# Sheet1.net
KiCad netlist of a schematic drawn in Altium Designer
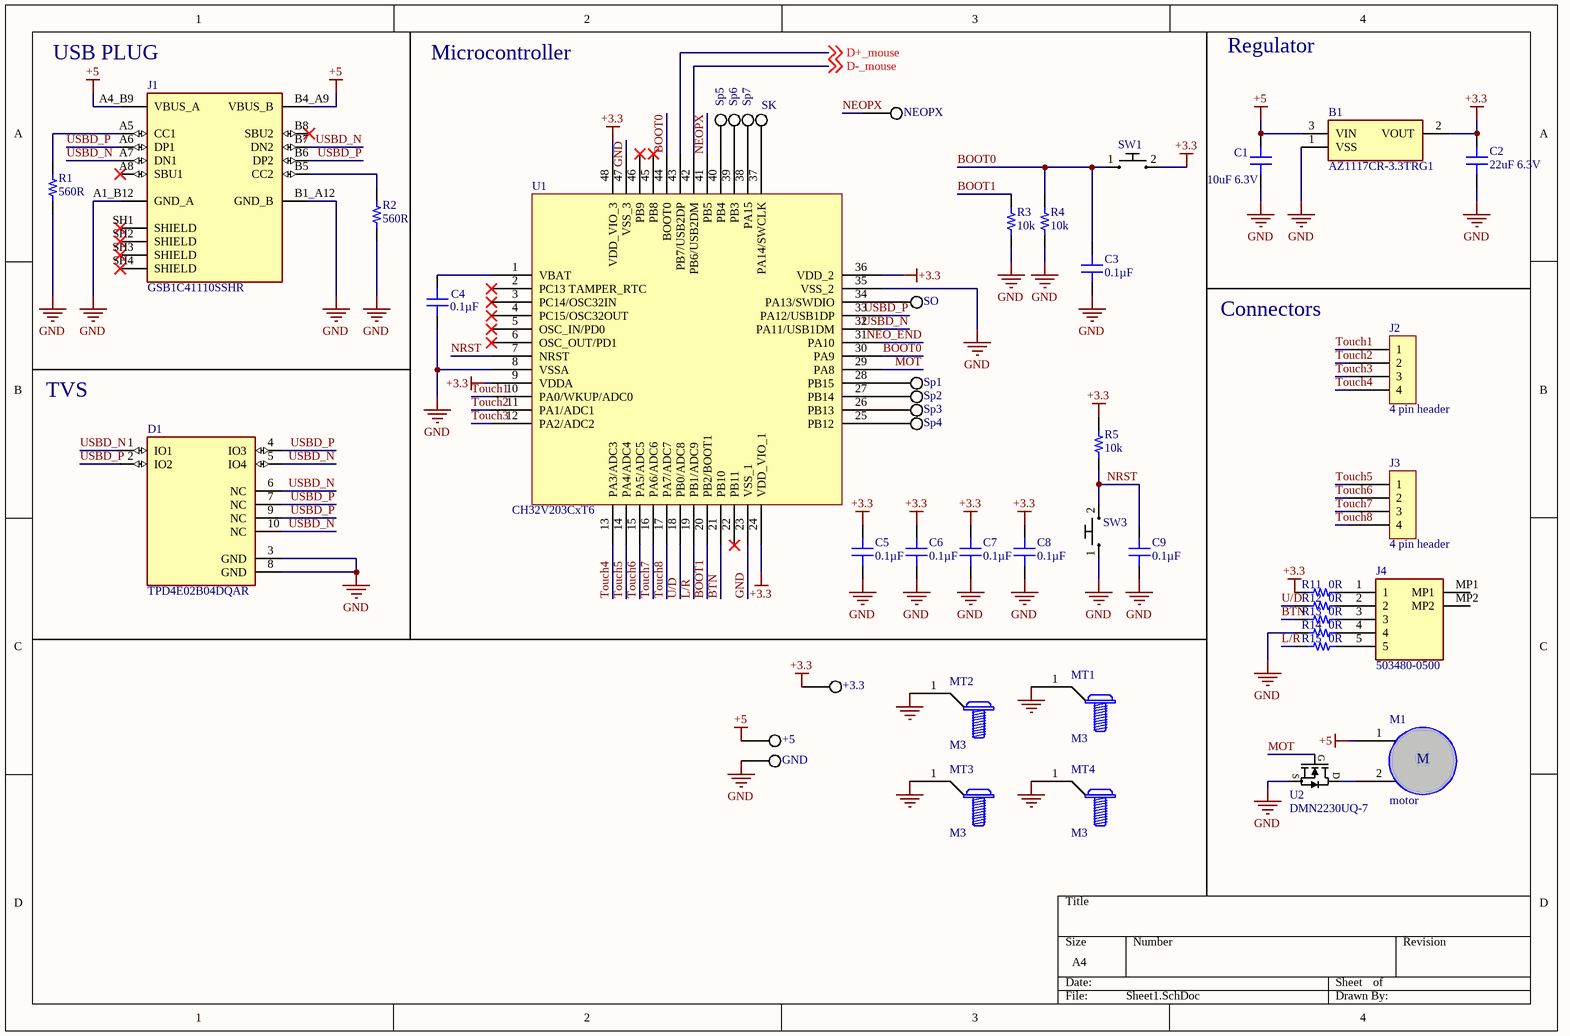
[diagram p0: Sheet1.SchDoc]

(export (version "E")
  (design (tool "Eeschema 10.0.6"))
  (components
    (comp (ref "+3.3")
      (value "TestPoint")
      (footprint "TP2020")
      (description "PC TEST POINT MINIATURE")
      (fields (field (name "PART NUMBER") "JMP-RTZL7I") (field (name "MANUFACTURER") "Keystone Electronics"))
      (libsource (lib "Database_Libs_RenaudG") (part "TestPoint"))
    )
    (comp (ref "+5")
      (value "TestPoint")
      (footprint "TP2020")
      (description "PC TEST POINT MINIATURE")
      (fields (field (name "PART NUMBER") "JMP-RTZL7I") (field (name "MANUFACTURER") "Keystone Electronics"))
      (libsource (lib "Database_Libs_RenaudG") (part "TestPoint"))
    )
    (comp (ref "B1")
      (value "AZ1117CR-3.3TRG1")
      (footprint "SOT89-3")
      (description "3.3v LDO Voltage regulator")
      (fields
        (field (name "MOUSER PART NUMBER") "865-XC6206P331MR-G")
        (field (name "MANUFACTURER_PART_NUMBER") "XC6206P331MR-G")
      )
      (libsource (lib "Database_Libs_RenaudG") (part "AZ1117CR-3.3TRG1"))
    )
    (comp (ref "C1")
      (value "10uF 6.3V")
      (footprint "CAP 0603_1608")
      (description "CAP CER 10uF")
      (fields (field (name "PART NUMBER") "CAP0603-RU10OA") (field (name "MANUFACTURER") "YAGEO"))
      (libsource (lib "Database_Libs_RenaudG") (part "Capacitor"))
    )
    (comp (ref "C2")
      (value "22uF 6.3V")
      (footprint "CAP 0603_1608")
      (description "6.3V 22uF X5R ±20% 0603 Multilayer Ceramic Capacitors MLCC - SMD/SMT ROHS")
      (fields
        (field (name "PART NUMBER") "CAP0603-SAQ85G")
        (field (name "MANUFACTURER") "Samsung Electro-Mechanics")
      )
      (libsource (lib "Database_Libs_RenaudG") (part "Capacitor"))
    )
    (comp (ref "C3")
      (value "0.1µF")
      (footprint "CAP 0603_1608")
      (description "CAP CER SMD 0603 .1UF 10% X7R 25")
      (fields
        (field (name "PART NUMBER") "CAP-RTZP49")
        (field (name "MANUFACTURER") "Samsung Electro-Mechanics")
      )
      (libsource (lib "Database_Libs_RenaudG") (part "Capacitor"))
    )
    (comp (ref "C4")
      (value "0.1µF")
      (footprint "CAP 0603_1608")
      (description "CAP CER SMD 0603 .1UF 10% X7R 25")
      (fields
        (field (name "PART NUMBER") "CAP-RTZP49")
        (field (name "MANUFACTURER") "Samsung Electro-Mechanics")
      )
      (libsource (lib "Database_Libs_RenaudG") (part "Capacitor"))
    )
    (comp (ref "C5")
      (value "0.1µF")
      (footprint "CAP 0603_1608")
      (description "CAP CER SMD 0603 .1UF 10% X7R 25")
      (fields
        (field (name "PART NUMBER") "CAP-RTZP49")
        (field (name "MANUFACTURER") "Samsung Electro-Mechanics")
      )
      (libsource (lib "Database_Libs_RenaudG") (part "Capacitor"))
    )
    (comp (ref "C6")
      (value "0.1µF")
      (footprint "CAP 0603_1608")
      (description "CAP CER SMD 0603 .1UF 10% X7R 25")
      (fields
        (field (name "PART NUMBER") "CAP-RTZP49")
        (field (name "MANUFACTURER") "Samsung Electro-Mechanics")
      )
      (libsource (lib "Database_Libs_RenaudG") (part "Capacitor"))
    )
    (comp (ref "C7")
      (value "0.1µF")
      (footprint "CAP 0603_1608")
      (description "CAP CER SMD 0603 .1UF 10% X7R 25")
      (fields
        (field (name "PART NUMBER") "CAP-RTZP49")
        (field (name "MANUFACTURER") "Samsung Electro-Mechanics")
      )
      (libsource (lib "Database_Libs_RenaudG") (part "Capacitor"))
    )
    (comp (ref "C8")
      (value "0.1µF")
      (footprint "CAP 0603_1608")
      (description "CAP CER SMD 0603 .1UF 10% X7R 25")
      (fields
        (field (name "PART NUMBER") "CAP-RTZP49")
        (field (name "MANUFACTURER") "Samsung Electro-Mechanics")
      )
      (libsource (lib "Database_Libs_RenaudG") (part "Capacitor"))
    )
    (comp (ref "C9")
      (value "0.1µF")
      (footprint "CAP 0603_1608")
      (description "CAP CER SMD 0603 .1UF 10% X7R 25")
      (fields
        (field (name "PART NUMBER") "CAP-RTZP49")
        (field (name "MANUFACTURER") "Samsung Electro-Mechanics")
      )
      (libsource (lib "Database_Libs_RenaudG") (part "Capacitor"))
    )
    (comp (ref "D1")
      (value "TPD4E02B04DQAR")
      (footprint "DIO_TPD4E02B04DQAR")
      (description "ESD protection diode")
      (fields (field (name "MF") "Texas Instruments") (field (name "DIGI-KEY_PART_NUMBER") "296-43875-1-ND"))
      (libsource (lib "Database_Libs_RenaudG") (part "TPD4E02B04DQAR"))
    )
    (comp (ref "GND")
      (value "TestPoint")
      (footprint "TP2020")
      (description "PC TEST POINT MINIATURE")
      (fields (field (name "PART NUMBER") "JMP-RTZL7I") (field (name "MANUFACTURER") "Keystone Electronics"))
      (libsource (lib "Database_Libs_RenaudG") (part "TestPoint"))
    )
    (comp (ref "J1")
      (value "GSB1C41110SSHR")
      (footprint "AMPHENOL_GSB1C41110SSHR")
      (description "16 pin usb type c right angle female connector")
      (fields (field (name "MF") "Amphenol Canada") (field (name "PART NUMBER") "USB_16p_SMT"))
      (libsource (lib "Database_Libs_RenaudG") (part "GSB1C41110SSHR"))
    )
    (comp (ref "J2")
      (value "4 pin header")
      (footprint "4 pin header")
      (fields
        (field (name "PART NUMBER") "4PinHeader")
        (field (name "MANUFACTURER") "Sullins Connector Solutions")
      )
      (libsource (lib "Database_Libs_RenaudG") (part "4 pin conn"))
    )
    (comp (ref "J3")
      (value "4 pin header")
      (footprint "4 pin header")
      (fields
        (field (name "PART NUMBER") "4PinHeader")
        (field (name "MANUFACTURER") "Sullins Connector Solutions")
      )
      (libsource (lib "Database_Libs_RenaudG") (part "4 pin conn"))
    )
    (comp (ref "J4")
      (value "503480-0500")
      (footprint "SamacSys:5034800500")
      (description "Connector")
      (fields (field (name "MOUSER PART NUMBER") "538-503480-0500"))
      (libsource (lib "*") (part "503480-0500"))
    )
    (comp (ref "M1")
      (value "motor")
      (footprint "2 pin header")
      (description "Vibrating motor")
      (fields (field (name "PART NUMBER") "VibrationMotor") (field (name "MANUFACTURER") "ChingChong"))
      (libsource (lib "Database_Libs_RenaudG") (part "motor"))
    )
    (comp (ref "MT1")
      (value "M3")
      (footprint "M3_MT_HOLE")
      (description "M3 pounting screw")
      (fields (field (name "PART NUMBER") "NSP-M3"))
      (libsource (lib "Database_Libs_RenaudG") (part "Mouting Hole"))
    )
    (comp (ref "MT2")
      (value "M3")
      (footprint "M3_MT_HOLE")
      (description "M3 pounting screw")
      (fields (field (name "PART NUMBER") "NSP-M3"))
      (libsource (lib "Database_Libs_RenaudG") (part "Mouting Hole"))
    )
    (comp (ref "MT3")
      (value "M3")
      (footprint "M3_MT_HOLE")
      (description "M3 pounting screw")
      (fields (field (name "PART NUMBER") "NSP-M3"))
      (libsource (lib "Database_Libs_RenaudG") (part "Mouting Hole"))
    )
    (comp (ref "MT4")
      (value "M3")
      (footprint "M3_MT_HOLE")
      (description "M3 pounting screw")
      (fields (field (name "PART NUMBER") "NSP-M3"))
      (libsource (lib "Database_Libs_RenaudG") (part "Mouting Hole"))
    )
    (comp (ref "NEOPX")
      (value "TestPoint")
      (footprint "TP2020")
      (description "PC TEST POINT MINIATURE")
      (fields (field (name "PART NUMBER") "JMP-RTZL7I") (field (name "MANUFACTURER") "Keystone Electronics"))
      (libsource (lib "Database_Libs_RenaudG") (part "TestPoint"))
    )
    (comp (ref "R1")
      (value "560R")
      (footprint "RES 0603_1608")
      (description "RES SMD 560 OHM 1% 1/10W 0603")
      (fields
        (field (name "PART NUMBER") "RES-RTZP5N")
        (field (name "MANUFACTURER") "Panasonic Electronic Components")
      )
      (libsource (lib "Database_Libs_RenaudG") (part "Resistor"))
    )
    (comp (ref "R2")
      (value "560R")
      (footprint "RES 0603_1608")
      (description "RES SMD 560 OHM 1% 1/10W 0603")
      (fields
        (field (name "PART NUMBER") "RES-RTZP5N")
        (field (name "MANUFACTURER") "Panasonic Electronic Components")
      )
      (libsource (lib "Database_Libs_RenaudG") (part "Resistor"))
    )
    (comp (ref "R3")
      (value "10k")
      (footprint "RES 0603_1608")
      (description "RES SMD 10K OHM 1% 1/10W 0603")
      (fields
        (field (name "PART NUMBER") "RES-RTZP5R")
        (field (name "MANUFACTURER") "Panasonic Electronic Components")
      )
      (libsource (lib "Database_Libs_RenaudG") (part "Resistor"))
    )
    (comp (ref "R4")
      (value "10k")
      (footprint "RES 0603_1608")
      (description "RES SMD 10K OHM 1% 1/10W 0603")
      (fields
        (field (name "PART NUMBER") "RES-RTZP5R")
        (field (name "MANUFACTURER") "Panasonic Electronic Components")
      )
      (libsource (lib "Database_Libs_RenaudG") (part "Resistor"))
    )
    (comp (ref "R5")
      (value "10k")
      (footprint "RES 0603_1608")
      (description "RES SMD 10K OHM 1% 1/10W 0603")
      (fields
        (field (name "PART NUMBER") "RES-RTZP5R")
        (field (name "MANUFACTURER") "Panasonic Electronic Components")
      )
      (libsource (lib "Database_Libs_RenaudG") (part "Resistor"))
    )
    (comp (ref "R11")
      (value "0R")
      (footprint "RES 0603_1608")
      (description "RES SMD 0 OHM JUMPER 1/10W 0603")
      (fields
        (field (name "PART NUMBER") "ERJ-3GEY0R00V")
        (field (name "MANUFACTURER") "Panasonic Electronic Components")
      )
      (libsource (lib "Database_Libs_RenaudG") (part "Resistor"))
    )
    (comp (ref "R12")
      (value "0R")
      (footprint "RES 0603_1608")
      (description "RES SMD 0 OHM JUMPER 1/10W 0603")
      (fields
        (field (name "PART NUMBER") "ERJ-3GEY0R00V")
        (field (name "MANUFACTURER") "Panasonic Electronic Components")
      )
      (libsource (lib "Database_Libs_RenaudG") (part "Resistor"))
    )
    (comp (ref "R13")
      (value "0R")
      (footprint "RES 0603_1608")
      (description "RES SMD 0 OHM JUMPER 1/10W 0603")
      (fields
        (field (name "PART NUMBER") "ERJ-3GEY0R00V")
        (field (name "MANUFACTURER") "Panasonic Electronic Components")
      )
      (libsource (lib "Database_Libs_RenaudG") (part "Resistor"))
    )
    (comp (ref "R14")
      (value "0R")
      (footprint "RES 0603_1608")
      (description "RES SMD 0 OHM JUMPER 1/10W 0603")
      (fields
        (field (name "PART NUMBER") "ERJ-3GEY0R00V")
        (field (name "MANUFACTURER") "Panasonic Electronic Components")
      )
      (libsource (lib "Database_Libs_RenaudG") (part "Resistor"))
    )
    (comp (ref "R15")
      (value "0R")
      (footprint "RES 0603_1608")
      (description "RES SMD 0 OHM JUMPER 1/10W 0603")
      (fields
        (field (name "PART NUMBER") "ERJ-3GEY0R00V")
        (field (name "MANUFACTURER") "Panasonic Electronic Components")
      )
      (libsource (lib "Database_Libs_RenaudG") (part "Resistor"))
    )
    (comp (ref "SK")
      (value "TestPoint")
      (footprint "TP2020")
      (description "PC TEST POINT MINIATURE")
      (fields (field (name "PART NUMBER") "JMP-RTZL7I") (field (name "MANUFACTURER") "Keystone Electronics"))
      (libsource (lib "Database_Libs_RenaudG") (part "TestPoint"))
    )
    (comp (ref "SO")
      (value "TestPoint")
      (footprint "TP2020")
      (description "PC TEST POINT MINIATURE")
      (fields (field (name "PART NUMBER") "JMP-RTZL7I") (field (name "MANUFACTURER") "Keystone Electronics"))
      (libsource (lib "Database_Libs_RenaudG") (part "TestPoint"))
    )
    (comp (ref "Sp1")
      (value "TestPoint")
      (footprint "TP2020")
      (description "PC TEST POINT MINIATURE")
      (fields (field (name "PART NUMBER") "JMP-RTZL7I") (field (name "MANUFACTURER") "Keystone Electronics"))
      (libsource (lib "Database_Libs_RenaudG") (part "TestPoint"))
    )
    (comp (ref "Sp2")
      (value "TestPoint")
      (footprint "TP2020")
      (description "PC TEST POINT MINIATURE")
      (fields (field (name "PART NUMBER") "JMP-RTZL7I") (field (name "MANUFACTURER") "Keystone Electronics"))
      (libsource (lib "Database_Libs_RenaudG") (part "TestPoint"))
    )
    (comp (ref "Sp3")
      (value "TestPoint")
      (footprint "TP2020")
      (description "PC TEST POINT MINIATURE")
      (fields (field (name "PART NUMBER") "JMP-RTZL7I") (field (name "MANUFACTURER") "Keystone Electronics"))
      (libsource (lib "Database_Libs_RenaudG") (part "TestPoint"))
    )
    (comp (ref "Sp4")
      (value "TestPoint")
      (footprint "TP2020")
      (description "PC TEST POINT MINIATURE")
      (fields (field (name "PART NUMBER") "JMP-RTZL7I") (field (name "MANUFACTURER") "Keystone Electronics"))
      (libsource (lib "Database_Libs_RenaudG") (part "TestPoint"))
    )
    (comp (ref "Sp5")
      (value "TestPoint")
      (footprint "TP2020")
      (description "PC TEST POINT MINIATURE")
      (fields (field (name "PART NUMBER") "JMP-RTZL7I") (field (name "MANUFACTURER") "Keystone Electronics"))
      (libsource (lib "Database_Libs_RenaudG") (part "TestPoint"))
    )
    (comp (ref "Sp6")
      (value "TestPoint")
      (footprint "TP2020")
      (description "PC TEST POINT MINIATURE")
      (fields (field (name "PART NUMBER") "JMP-RTZL7I") (field (name "MANUFACTURER") "Keystone Electronics"))
      (libsource (lib "Database_Libs_RenaudG") (part "TestPoint"))
    )
    (comp (ref "Sp7")
      (value "TestPoint")
      (footprint "TP2020")
      (description "PC TEST POINT MINIATURE")
      (fields (field (name "PART NUMBER") "JMP-RTZL7I") (field (name "MANUFACTURER") "Keystone Electronics"))
      (libsource (lib "Database_Libs_RenaudG") (part "TestPoint"))
    )
    (comp (ref "SW1")
      (value "SPST_BUTTON")
      (footprint "3x4mmBTN")
      (description "50mA Brick nogging SPST 12V SMD,3x4mm Tactile Switches ROHS")
      (fields (field (name "PART NUMBER") "BTN-000001") (field (name "MANUFACTURER") "XUNPU\r\nXUNPU"))
      (libsource (lib "Database_Libs_RenaudG") (part "SPST_BUTTON"))
    )
    (comp (ref "SW3")
      (value "SPST_BUTTON")
      (footprint "3x4mmBTN")
      (description "50mA Brick nogging SPST 12V SMD,3x4mm Tactile Switches ROHS")
      (fields (field (name "PART NUMBER") "BTN-000001") (field (name "MANUFACTURER") "XUNPU\r\nXUNPU"))
      (libsource (lib "Database_Libs_RenaudG") (part "SPST_BUTTON"))
    )
    (comp (ref "U1")
      (value "CH32V203CxT6")
      (footprint "LQFP48")
      (description "32bit RISC-V MCU 144MHz")
      (fields (field (name "PART NUMBER") "MCU-RV4Q62") (field (name "MANUFACTURER") "WCH-IC"))
      (libsource (lib "Database_Libs_RenaudG") (part "CH32V203CxT6"))
    )
    (comp (ref "U2")
      (value "DMN2230UQ-7")
      (footprint "DMN2230UQ_DIO-M")
      (description "NPN mosfet")
      (libsource (lib "Database_Libs_RenaudG") (part "DMN2230UQ-7"))
    )
  )
  (nets
    (net (code "1") (name "+3.3") (class "Default")
      (node (ref "+3.3") (pin "TP") (pintype "passive"))
      (node (ref "B1") (pin "2") (pinfunction "VOUT_2") (pintype "passive"))
      (node (ref "C2") (pin "2") (pinfunction "2_2") (pintype "passive"))
      (node (ref "C5") (pin "2") (pinfunction "2_2") (pintype "passive"))
      (node (ref "C6") (pin "2") (pinfunction "2_2") (pintype "passive"))
      (node (ref "C7") (pin "2") (pinfunction "2_2") (pintype "passive"))
      (node (ref "C8") (pin "2") (pinfunction "2_2") (pintype "passive"))
      (node (ref "R11") (pin "1") (pinfunction "1_1") (pintype "passive"))
      (node (ref "R5") (pin "2") (pinfunction "2_2") (pintype "passive"))
      (node (ref "SW1") (pin "2") (pinfunction "2_2") (pintype "passive"))
      (node (ref "U1") (pin "24") (pinfunction "VDD_VIO_1_24") (pintype "passive"))
      (node (ref "U1") (pin "36") (pinfunction "VDD_2_36") (pintype "passive"))
      (node (ref "U1") (pin "48") (pinfunction "VDD_VIO_3_48") (pintype "passive"))
      (node (ref "U1") (pin "9") (pinfunction "VDDA_9") (pintype "passive"))
    )
    (net (code "2") (name "+5") (class "Default")
      (node (ref "+5") (pin "TP") (pintype "passive"))
      (node (ref "B1") (pin "3") (pinfunction "VIN_3") (pintype "passive"))
      (node (ref "C1") (pin "2") (pinfunction "2_2") (pintype "passive"))
      (node (ref "J1") (pin "A4_B9") (pinfunction "VBUS_A_A4_B9") (pintype "power_in"))
      (node (ref "J1") (pin "B4_A9") (pinfunction "VBUS_B_B4_A9") (pintype "power_in"))
      (node (ref "M1") (pin "1") (pintype "passive"))
    )
    (net (code "3") (name "/BOOT0") (class "Default")
      (node (ref "C3") (pin "2") (pinfunction "2_2") (pintype "passive"))
      (node (ref "R4") (pin "2") (pinfunction "2_2") (pintype "passive"))
      (node (ref "SW1") (pin "1") (pinfunction "1_1") (pintype "passive"))
      (node (ref "U1") (pin "30") (pinfunction "PA9_30") (pintype "passive"))
      (node (ref "U1") (pin "44") (pinfunction "BOOT0_44") (pintype "passive"))
    )
    (net (code "4") (name "/BOOT1") (class "Default")
      (node (ref "R3") (pin "2") (pinfunction "2_2") (pintype "passive"))
      (node (ref "U1") (pin "20") (pinfunction "PB2/BOOT1_20") (pintype "passive"))
    )
    (net (code "5") (name "/BTN") (class "Default")
      (node (ref "R13") (pin "1") (pinfunction "1_1") (pintype "passive"))
      (node (ref "U1") (pin "21") (pinfunction "PB10_21") (pintype "passive"))
    )
    (net (code "6") (name "/L{slash}R") (class "Default")
      (node (ref "R15") (pin "1") (pinfunction "1_1") (pintype "passive"))
      (node (ref "U1") (pin "19") (pinfunction "PB1/ADC9_19") (pintype "passive"))
    )
    (net (code "7") (name "/MOT") (class "Default")
      (node (ref "U1") (pin "29") (pinfunction "PA8_29") (pintype "passive"))
      (node (ref "U2") (pin "2") (pinfunction "G_2") (pintype "passive"))
    )
    (net (code "8") (name "/NEOPX") (class "Default")
      (node (ref "NEOPX") (pin "TP") (pintype "passive"))
      (node (ref "U1") (pin "41") (pinfunction "PB5_41") (pintype "passive"))
    )
    (net (code "9") (name "/NEO_END") (class "Default")
      (node (ref "U1") (pin "31") (pinfunction "PA10_31") (pintype "passive"))
    )
    (net (code "10") (name "/NRST") (class "Default")
      (node (ref "C9") (pin "2") (pinfunction "2_2") (pintype "passive"))
      (node (ref "R5") (pin "1") (pinfunction "1_1") (pintype "passive"))
      (node (ref "SW3") (pin "2") (pinfunction "2_2") (pintype "passive"))
      (node (ref "U1") (pin "7") (pinfunction "NRST_7") (pintype "passive"))
    )
    (net (code "11") (name "/Touch1") (class "Default")
      (node (ref "J2") (pin "1") (pinfunction "1_1") (pintype "passive"))
      (node (ref "U1") (pin "10") (pinfunction "PA0/WKUP/ADC0_10") (pintype "passive"))
    )
    (net (code "12") (name "/Touch2") (class "Default")
      (node (ref "J2") (pin "2") (pinfunction "2_2") (pintype "passive"))
      (node (ref "U1") (pin "11") (pinfunction "PA1/ADC1_11") (pintype "passive"))
    )
    (net (code "13") (name "/Touch3") (class "Default")
      (node (ref "J2") (pin "3") (pinfunction "3_3") (pintype "passive"))
      (node (ref "U1") (pin "12") (pinfunction "PA2/ADC2_12") (pintype "passive"))
    )
    (net (code "14") (name "/Touch4") (class "Default")
      (node (ref "J2") (pin "4") (pinfunction "4_4") (pintype "passive"))
      (node (ref "U1") (pin "13") (pinfunction "PA3/ADC3_13") (pintype "passive"))
    )
    (net (code "15") (name "/Touch5") (class "Default")
      (node (ref "J3") (pin "1") (pinfunction "1_1") (pintype "passive"))
      (node (ref "U1") (pin "14") (pinfunction "PA4/ADC4_14") (pintype "passive"))
    )
    (net (code "16") (name "/Touch6") (class "Default")
      (node (ref "J3") (pin "2") (pinfunction "2_2") (pintype "passive"))
      (node (ref "U1") (pin "15") (pinfunction "PA5/ADC5_15") (pintype "passive"))
    )
    (net (code "17") (name "/Touch7") (class "Default")
      (node (ref "J3") (pin "3") (pinfunction "3_3") (pintype "passive"))
      (node (ref "U1") (pin "16") (pinfunction "PA6/ADC6_16") (pintype "passive"))
    )
    (net (code "18") (name "/Touch8") (class "Default")
      (node (ref "J3") (pin "4") (pinfunction "4_4") (pintype "passive"))
      (node (ref "U1") (pin "17") (pinfunction "PA7/ADC7_17") (pintype "passive"))
    )
    (net (code "19") (name "/USBD_N") (class "Default")
      (node (ref "D1") (pin "1") (pinfunction "IO1_1") (pintype "bidirectional"))
      (node (ref "D1") (pin "10") (pinfunction "NC_10") (pintype "passive"))
      (node (ref "D1") (pin "5") (pinfunction "IO4_5") (pintype "bidirectional"))
      (node (ref "D1") (pin "6") (pinfunction "NC_6") (pintype "passive"))
      (node (ref "J1") (pin "A7") (pinfunction "DN1_A7") (pintype "bidirectional"))
      (node (ref "J1") (pin "B7") (pinfunction "DN2_B7") (pintype "bidirectional"))
      (node (ref "U1") (pin "32") (pinfunction "PA11/USB1DM_32") (pintype "passive"))
    )
    (net (code "20") (name "/USBD_P") (class "Default")
      (node (ref "D1") (pin "2") (pinfunction "IO2_2") (pintype "bidirectional"))
      (node (ref "D1") (pin "4") (pinfunction "IO3_4") (pintype "bidirectional"))
      (node (ref "D1") (pin "7") (pinfunction "NC_7") (pintype "passive"))
      (node (ref "D1") (pin "9") (pinfunction "NC_9") (pintype "passive"))
      (node (ref "J1") (pin "A6") (pinfunction "DP1_A6") (pintype "bidirectional"))
      (node (ref "J1") (pin "B6") (pinfunction "DP2_B6") (pintype "bidirectional"))
      (node (ref "U1") (pin "33") (pinfunction "PA12/USB1DP_33") (pintype "passive"))
    )
    (net (code "21") (name "/U{slash}D") (class "Default")
      (node (ref "R12") (pin "1") (pinfunction "1_1") (pintype "passive"))
      (node (ref "U1") (pin "18") (pinfunction "PB0/ADC8_18") (pintype "passive"))
    )
    (net (code "22") (name "D+_mouse") (class "Default")
      (node (ref "U1") (pin "43") (pinfunction "PB7/USB2DP_43") (pintype "passive"))
    )
    (net (code "23") (name "D-_mouse") (class "Default")
      (node (ref "U1") (pin "42") (pinfunction "PB6/USB2DM_42") (pintype "passive"))
    )
    (net (code "24") (name "GND") (class "Default")
      (node (ref "B1") (pin "1") (pinfunction "VSS_1") (pintype "passive"))
      (node (ref "C1") (pin "1") (pinfunction "1_1") (pintype "passive"))
      (node (ref "C2") (pin "1") (pinfunction "1_1") (pintype "passive"))
      (node (ref "C3") (pin "1") (pinfunction "1_1") (pintype "passive"))
      (node (ref "C4") (pin "1") (pinfunction "1_1") (pintype "passive"))
      (node (ref "C5") (pin "1") (pinfunction "1_1") (pintype "passive"))
      (node (ref "C6") (pin "1") (pinfunction "1_1") (pintype "passive"))
      (node (ref "C7") (pin "1") (pinfunction "1_1") (pintype "passive"))
      (node (ref "C8") (pin "1") (pinfunction "1_1") (pintype "passive"))
      (node (ref "C9") (pin "1") (pinfunction "1_1") (pintype "passive"))
      (node (ref "D1") (pin "3") (pinfunction "GND_3") (pintype "power_in"))
      (node (ref "D1") (pin "8") (pinfunction "GND_8") (pintype "power_in"))
      (node (ref "GND") (pin "TP") (pintype "passive"))
      (node (ref "J1") (pin "A1_B12") (pinfunction "GND_A_A1_B12") (pintype "power_in"))
      (node (ref "J1") (pin "B1_A12") (pinfunction "GND_B_B1_A12") (pintype "power_in"))
      (node (ref "MT1") (pin "1") (pinfunction "0_1") (pintype "passive"))
      (node (ref "MT2") (pin "1") (pinfunction "0_1") (pintype "passive"))
      (node (ref "MT3") (pin "1") (pinfunction "0_1") (pintype "passive"))
      (node (ref "MT4") (pin "1") (pinfunction "0_1") (pintype "passive"))
      (node (ref "R1") (pin "1") (pinfunction "1_1") (pintype "passive"))
      (node (ref "R14") (pin "1") (pinfunction "1_1") (pintype "passive"))
      (node (ref "R2") (pin "1") (pinfunction "1_1") (pintype "passive"))
      (node (ref "R3") (pin "1") (pinfunction "1_1") (pintype "passive"))
      (node (ref "R4") (pin "1") (pinfunction "1_1") (pintype "passive"))
      (node (ref "SW3") (pin "1") (pinfunction "1_1") (pintype "passive"))
      (node (ref "U1") (pin "23") (pinfunction "VSS_1_23") (pintype "passive"))
      (node (ref "U1") (pin "35") (pinfunction "VSS_2_35") (pintype "passive"))
      (node (ref "U1") (pin "47") (pinfunction "VSS_3_47") (pintype "passive"))
      (node (ref "U1") (pin "8") (pinfunction "VSSA_8") (pintype "passive"))
      (node (ref "U2") (pin "3") (pinfunction "S_3") (pintype "passive"))
    )
    (net (code "25") (name "Net-(J1-CC1)") (class "Default")
      (node (ref "J1") (pin "A5") (pinfunction "CC1_A5") (pintype "bidirectional"))
      (node (ref "R1") (pin "2") (pinfunction "2_2") (pintype "passive"))
    )
    (net (code "26") (name "Net-(J1-CC2)") (class "Default")
      (node (ref "J1") (pin "B5") (pinfunction "CC2_B5") (pintype "bidirectional"))
      (node (ref "R2") (pin "2") (pinfunction "2_2") (pintype "passive"))
    )
    (net (code "27") (name "Net-(J4-Pad1)") (class "Default")
      (node (ref "J4") (pin "1") (pinfunction "1_1") (pintype "passive"))
      (node (ref "R11") (pin "2") (pinfunction "2_2") (pintype "passive"))
    )
    (net (code "28") (name "Net-(J4-Pad2)") (class "Default")
      (node (ref "J4") (pin "2") (pinfunction "2_2") (pintype "passive"))
      (node (ref "R12") (pin "2") (pinfunction "2_2") (pintype "passive"))
    )
    (net (code "29") (name "Net-(J4-Pad3)") (class "Default")
      (node (ref "J4") (pin "3") (pinfunction "3_3") (pintype "passive"))
      (node (ref "R13") (pin "2") (pinfunction "2_2") (pintype "passive"))
    )
    (net (code "30") (name "Net-(J4-Pad4)") (class "Default")
      (node (ref "J4") (pin "4") (pinfunction "4_4") (pintype "passive"))
      (node (ref "R14") (pin "2") (pinfunction "2_2") (pintype "passive"))
    )
    (net (code "31") (name "Net-(J4-Pad5)") (class "Default")
      (node (ref "J4") (pin "5") (pinfunction "5_5") (pintype "passive"))
      (node (ref "R15") (pin "2") (pinfunction "2_2") (pintype "passive"))
    )
    (net (code "32") (name "Net-(U1-PA13{slash}SWDIO)") (class "Default")
      (node (ref "SO") (pin "TP") (pintype "passive"))
      (node (ref "U1") (pin "34") (pinfunction "PA13/SWDIO_34") (pintype "passive"))
    )
    (net (code "33") (name "Net-(U1-PA14{slash}SWCLK)") (class "Default")
      (node (ref "SK") (pin "TP") (pintype "passive"))
      (node (ref "U1") (pin "37") (pinfunction "PA14/SWCLK_37") (pintype "passive"))
    )
    (net (code "34") (name "Net-(U1-PA15)") (class "Default")
      (node (ref "Sp7") (pin "TP") (pintype "passive"))
      (node (ref "U1") (pin "38") (pinfunction "PA15_38") (pintype "passive"))
    )
    (net (code "35") (name "Net-(U1-PB3)") (class "Default")
      (node (ref "Sp6") (pin "TP") (pintype "passive"))
      (node (ref "U1") (pin "39") (pinfunction "PB3_39") (pintype "passive"))
    )
    (net (code "36") (name "Net-(U1-PB4)") (class "Default")
      (node (ref "Sp5") (pin "TP") (pintype "passive"))
      (node (ref "U1") (pin "40") (pinfunction "PB4_40") (pintype "passive"))
    )
    (net (code "37") (name "Net-(U1-PB12)") (class "Default")
      (node (ref "Sp4") (pin "TP") (pintype "passive"))
      (node (ref "U1") (pin "25") (pinfunction "PB12_25") (pintype "passive"))
    )
    (net (code "38") (name "Net-(U1-PB13)") (class "Default")
      (node (ref "Sp3") (pin "TP") (pintype "passive"))
      (node (ref "U1") (pin "26") (pinfunction "PB13_26") (pintype "passive"))
    )
    (net (code "39") (name "Net-(U1-PB14)") (class "Default")
      (node (ref "Sp2") (pin "TP") (pintype "passive"))
      (node (ref "U1") (pin "27") (pinfunction "PB14_27") (pintype "passive"))
    )
    (net (code "40") (name "Net-(U1-PB15)") (class "Default")
      (node (ref "Sp1") (pin "TP") (pintype "passive"))
      (node (ref "U1") (pin "28") (pinfunction "PB15_28") (pintype "passive"))
    )
    (net (code "41") (name "Net-(U1-VBAT)") (class "Default")
      (node (ref "C4") (pin "2") (pinfunction "2_2") (pintype "passive"))
      (node (ref "U1") (pin "1") (pinfunction "VBAT_1") (pintype "passive"))
    )
    (net (code "42") (name "Net-(U2-D)") (class "Default")
      (node (ref "M1") (pin "2") (pintype "passive"))
      (node (ref "U2") (pin "1") (pinfunction "D_1") (pintype "passive"))
    )
    (net (code "43") (name "unconnected-(J1-SBU1-PadA8)") (class "Default")
      (node (ref "J1") (pin "A8") (pinfunction "SBU1_A8") (pintype "bidirectional+no_connect"))
    )
    (net (code "44") (name "unconnected-(J1-SBU2-PadB8)") (class "Default")
      (node (ref "J1") (pin "B8") (pinfunction "SBU2_B8") (pintype "bidirectional+no_connect"))
    )
    (net (code "45") (name "unconnected-(J1-SHIELD-PadSH1)") (class "Default")
      (node (ref "J1") (pin "SH1") (pinfunction "SHIELD_SH1") (pintype "passive+no_connect"))
    )
    (net (code "46") (name "unconnected-(J1-SHIELD-PadSH2)") (class "Default")
      (node (ref "J1") (pin "SH2") (pinfunction "SHIELD_SH2") (pintype "passive+no_connect"))
    )
    (net (code "47") (name "unconnected-(J1-SHIELD-PadSH3)") (class "Default")
      (node (ref "J1") (pin "SH3") (pinfunction "SHIELD_SH3") (pintype "passive+no_connect"))
    )
    (net (code "48") (name "unconnected-(J1-SHIELD-PadSH4)") (class "Default")
      (node (ref "J1") (pin "SH4") (pinfunction "SHIELD_SH4") (pintype "passive+no_connect"))
    )
    (net (code "49") (name "unconnected-(J4-PadMP1)") (class "Default")
      (node (ref "J4") (pin "MP1") (pinfunction "MP1_MP1") (pintype "passive"))
    )
    (net (code "50") (name "unconnected-(J4-PadMP2)") (class "Default")
      (node (ref "J4") (pin "MP2") (pinfunction "MP2_MP2") (pintype "passive"))
    )
    (net (code "51") (name "unconnected-(U1-OSC_IN{slash}PD0-Pad5)") (class "Default")
      (node (ref "U1") (pin "5") (pinfunction "OSC_IN/PD0_5") (pintype "passive+no_connect"))
    )
    (net (code "52") (name "unconnected-(U1-OSC_OUT{slash}PD1-Pad6)") (class "Default")
      (node (ref "U1") (pin "6") (pinfunction "OSC_OUT/PD1_6") (pintype "passive+no_connect"))
    )
    (net (code "53") (name "unconnected-(U1-PB8-Pad45)") (class "Default")
      (node (ref "U1") (pin "45") (pinfunction "PB8_45") (pintype "passive+no_connect"))
    )
    (net (code "54") (name "unconnected-(U1-PB9-Pad46)") (class "Default")
      (node (ref "U1") (pin "46") (pinfunction "PB9_46") (pintype "passive+no_connect"))
    )
    (net (code "55") (name "unconnected-(U1-PB11-Pad22)") (class "Default")
      (node (ref "U1") (pin "22") (pinfunction "PB11_22") (pintype "passive+no_connect"))
    )
    (net (code "56") (name "unconnected-(U1-PC13_TAMPER_RTC-Pad2)") (class "Default")
      (node (ref "U1") (pin "2") (pinfunction "PC13_TAMPER_RTC_2") (pintype "passive+no_connect"))
    )
    (net (code "57") (name "unconnected-(U1-PC14{slash}OSC32IN-Pad3)") (class "Default")
      (node (ref "U1") (pin "3") (pinfunction "PC14/OSC32IN_3") (pintype "passive+no_connect"))
    )
    (net (code "58") (name "unconnected-(U1-PC15{slash}OSC32OUT-Pad4)") (class "Default")
      (node (ref "U1") (pin "4") (pinfunction "PC15/OSC32OUT_4") (pintype "passive+no_connect"))
    )
  )
)
